# parakeet_board_rev_06.net
KiCad netlist of a schematic drawn in EAGLE
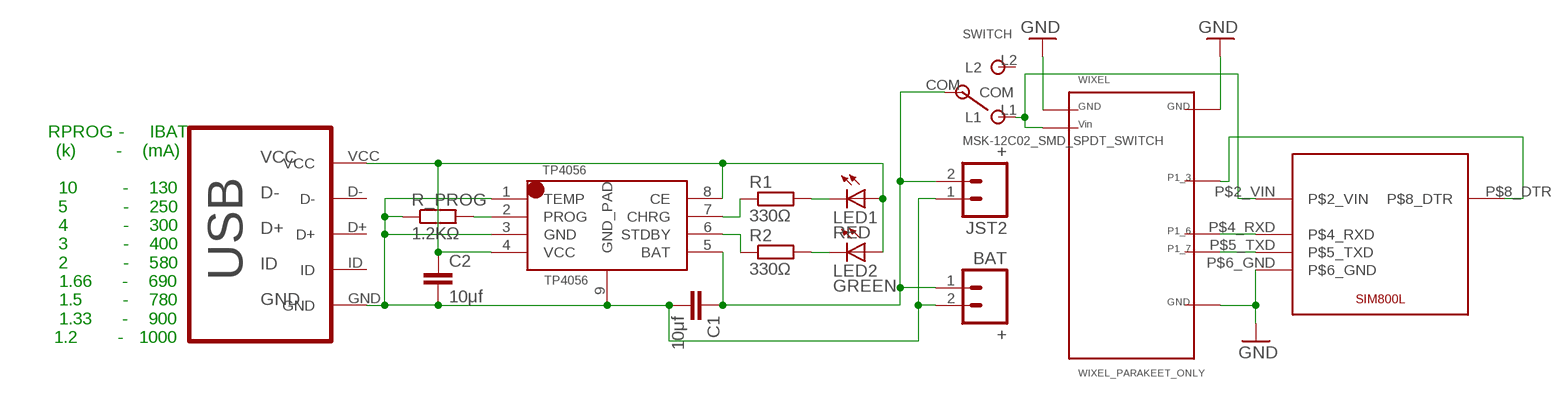
[diagram p0: schematic, sheet 1]

(export (version "E")
  (design (tool "Eeschema 10.0.6"))
  (components
    (comp (ref "+")
      (value "BAT")
      (footprint "eagle-import:1X02")
      (libsource (lib "eagle-import") (part "M02PTH"))
    )
    (comp (ref "C1")
      (value "10μf")
      (footprint "eagle-import:C1206")
      (libsource (lib "eagle-import") (part "C-EUC1206"))
    )
    (comp (ref "C2")
      (value "10μf")
      (footprint "eagle-import:C1206")
      (libsource (lib "eagle-import") (part "C-EUC1206"))
    )
    (comp (ref "JST2")
      (value "+")
      (footprint "eagle-import:JST-2-SMD")
      (libsource (lib "eagle-import") (part "M02-JST-2MM-SMT"))
    )
    (comp (ref "LED1")
      (value "RED")
      (footprint "eagle-import:CHIPLED_1206")
      (libsource (lib "eagle-import") (part "LEDCHIPLED_1206"))
    )
    (comp (ref "LED2")
      (value "GREEN")
      (footprint "eagle-import:CHIPLED_1206")
      (libsource (lib "eagle-import") (part "LEDCHIPLED_1206"))
    )
    (comp (ref "R1")
      (value "330Ω")
      (footprint "eagle-import:R1206")
      (libsource (lib "eagle-import") (part "R-EU_R1206"))
    )
    (comp (ref "R2")
      (value "330Ω")
      (footprint "eagle-import:R1206")
      (libsource (lib "eagle-import") (part "R-EU_R1206"))
    )
    (comp (ref "R_PROG")
      (value "1.2KΩ")
      (footprint "eagle-import:R1206")
      (libsource (lib "eagle-import") (part "R-EU_R1206"))
    )
    (comp (ref "SIM800L")
      (value "SIM800L_PARAKEET_ONLY")
      (footprint "eagle-import:SIM800L_PARAKEET_ONLY")
      (libsource (lib "eagle-import") (part "SIM800L_PARAKEET_ONLY"))
    )
    (comp (ref "SWITCH")
      (value "MSK-12C02_SMD_SPDT_SWITCH")
      (footprint "eagle-import:MSK-12C02")
      (libsource (lib "eagle-import") (part "MSK-12C02_SMD_SPDT_SWITCH"))
    )
    (comp (ref "TP4056")
      (value "TP4056")
      (footprint "eagle-import:SOP-8")
      (libsource (lib "eagle-import") (part "TP4056"))
    )
    (comp (ref "USB")
      (value "MICRO-USB-B")
      (footprint "eagle-import:MICRO_USB_4_LEGS")
      (libsource (lib "eagle-import") (part "MICRO-USB-B"))
    )
    (comp (ref "WIXEL")
      (value "WIXEL_PARAKEET_ONLY")
      (footprint "eagle-import:WIXEL_PARAKEET_ONLY")
      (libsource (lib "eagle-import") (part "WIXEL_PARAKEET_ONLY"))
    )
  )
  (nets
    (net (code "1") (name "GND") (class "Default")
      (node (ref "+") (pin "2") (pinfunction "2_2") (pintype "passive"))
      (node (ref "C1") (pin "2") (pinfunction "2_2") (pintype "passive"))
      (node (ref "C2") (pin "2") (pinfunction "2_2") (pintype "passive"))
      (node (ref "JST2") (pin "1") (pinfunction "2_1") (pintype "passive"))
      (node (ref "R_PROG") (pin "1") (pinfunction "1_1") (pintype "passive"))
      (node (ref "SIM800L") (pin "P$6_GND") (pinfunction "P$6_GND_P$6_GND") (pintype "bidirectional"))
      (node (ref "TP4056") (pin "1") (pinfunction "TEMP_1") (pintype "bidirectional"))
      (node (ref "TP4056") (pin "3") (pinfunction "GND_3") (pintype "bidirectional"))
      (node (ref "TP4056") (pin "9") (pinfunction "GND_PAD_9") (pintype "bidirectional"))
      (node (ref "USB") (pin "GND") (pinfunction "GND_GND") (pintype "bidirectional"))
      (node (ref "WIXEL") (pin "P$1") (pinfunction "P$1-GND1_P$1") (pintype "bidirectional"))
      (node (ref "WIXEL") (pin "P$12") (pinfunction "P$12-GND2_P$12") (pintype "bidirectional"))
      (node (ref "WIXEL") (pin "P$23") (pinfunction "P$23-GND3_P$23") (pintype "bidirectional"))
    )
    (net (code "2") (name "Net-(JST2-1)") (class "Default")
      (node (ref "+") (pin "1") (pinfunction "1_1") (pintype "passive"))
      (node (ref "C1") (pin "1") (pinfunction "1_1") (pintype "passive"))
      (node (ref "JST2") (pin "2") (pinfunction "1_2") (pintype "passive"))
      (node (ref "SWITCH") (pin "COM") (pinfunction "COM_COM") (pintype "bidirectional"))
      (node (ref "TP4056") (pin "5") (pinfunction "BAT_5") (pintype "bidirectional"))
    )
    (net (code "3") (name "Net-(LED1-PadC)") (class "Default")
      (node (ref "LED1") (pin "C") (pinfunction "C_C") (pintype "passive"))
      (node (ref "R1") (pin "2") (pinfunction "2_2") (pintype "passive"))
    )
    (net (code "4") (name "Net-(LED2-PadC)") (class "Default")
      (node (ref "LED2") (pin "C") (pinfunction "C_C") (pintype "passive"))
      (node (ref "R2") (pin "2") (pinfunction "2_2") (pintype "passive"))
    )
    (net (code "5") (name "Net-(TP4056-CE)") (class "Default")
      (node (ref "C2") (pin "1") (pinfunction "1_1") (pintype "passive"))
      (node (ref "LED1") (pin "A") (pinfunction "A_A") (pintype "passive"))
      (node (ref "LED2") (pin "A") (pinfunction "A_A") (pintype "passive"))
      (node (ref "TP4056") (pin "4") (pinfunction "VCC_4") (pintype "bidirectional"))
      (node (ref "TP4056") (pin "8") (pinfunction "CE_8") (pintype "bidirectional"))
      (node (ref "USB") (pin "VCC") (pinfunction "VCC_VCC") (pintype "bidirectional"))
    )
    (net (code "6") (name "Net-(TP4056-CHRG)") (class "Default")
      (node (ref "R1") (pin "1") (pinfunction "1_1") (pintype "passive"))
      (node (ref "TP4056") (pin "7") (pinfunction "CHRG_7") (pintype "bidirectional"))
    )
    (net (code "7") (name "Net-(TP4056-PROG)") (class "Default")
      (node (ref "R_PROG") (pin "2") (pinfunction "2_2") (pintype "passive"))
      (node (ref "TP4056") (pin "2") (pinfunction "PROG_2") (pintype "bidirectional"))
    )
    (net (code "8") (name "Net-(TP4056-STDBY)") (class "Default")
      (node (ref "R2") (pin "1") (pinfunction "1_1") (pintype "passive"))
      (node (ref "TP4056") (pin "6") (pinfunction "STDBY_6") (pintype "bidirectional"))
    )
    (net (code "9") (name "Net-(WIXEL-P$2-VIN)") (class "Default")
      (node (ref "SIM800L") (pin "P$2_VIN") (pinfunction "P$2_VIN_P$2_VIN") (pintype "bidirectional"))
      (node (ref "SWITCH") (pin "L1") (pinfunction "L1_L1") (pintype "bidirectional"))
      (node (ref "WIXEL") (pin "P$2") (pinfunction "P$2-VIN_P$2") (pintype "bidirectional"))
    )
    (net (code "10") (name "Net-(WIXEL-P$16-P1_3)") (class "Default")
      (node (ref "SIM800L") (pin "P$8_DTR") (pinfunction "P$8_DTR_P$8_DTR") (pintype "bidirectional"))
      (node (ref "WIXEL") (pin "P$16") (pinfunction "P$16-P1_3_P$16") (pintype "bidirectional"))
    )
    (net (code "11") (name "Net-(WIXEL-P$19-P1_6)") (class "Default")
      (node (ref "SIM800L") (pin "P$4_RXD") (pinfunction "P$4_RXD_P$4_RXD") (pintype "bidirectional"))
      (node (ref "WIXEL") (pin "P$19") (pinfunction "P$19-P1_6_P$19") (pintype "bidirectional"))
    )
    (net (code "12") (name "Net-(WIXEL-P$20-P1_7)") (class "Default")
      (node (ref "SIM800L") (pin "P$5_TXD") (pinfunction "P$5_TXD_P$5_TXD") (pintype "bidirectional"))
      (node (ref "WIXEL") (pin "P$20") (pinfunction "P$20-P1_7_P$20") (pintype "bidirectional"))
    )
    (net (code "13") (name "unconnected-(SWITCH-PadL2)") (class "Default")
      (node (ref "SWITCH") (pin "L2") (pinfunction "L2_L2") (pintype "bidirectional"))
    )
    (net (code "14") (name "unconnected-(USB-PadD+)") (class "Default")
      (node (ref "USB") (pin "D+") (pinfunction "D+_D+") (pintype "bidirectional"))
    )
    (net (code "15") (name "unconnected-(USB-PadD-)") (class "Default")
      (node (ref "USB") (pin "D-") (pinfunction "D-_D-") (pintype "bidirectional"))
    )
    (net (code "16") (name "unconnected-(USB-PadID)") (class "Default")
      (node (ref "USB") (pin "ID") (pinfunction "ID_ID") (pintype "bidirectional"))
    )
  )
)
